# AstroEQ_PTH_MK3.net
KiCad netlist of a schematic drawn in EAGLE
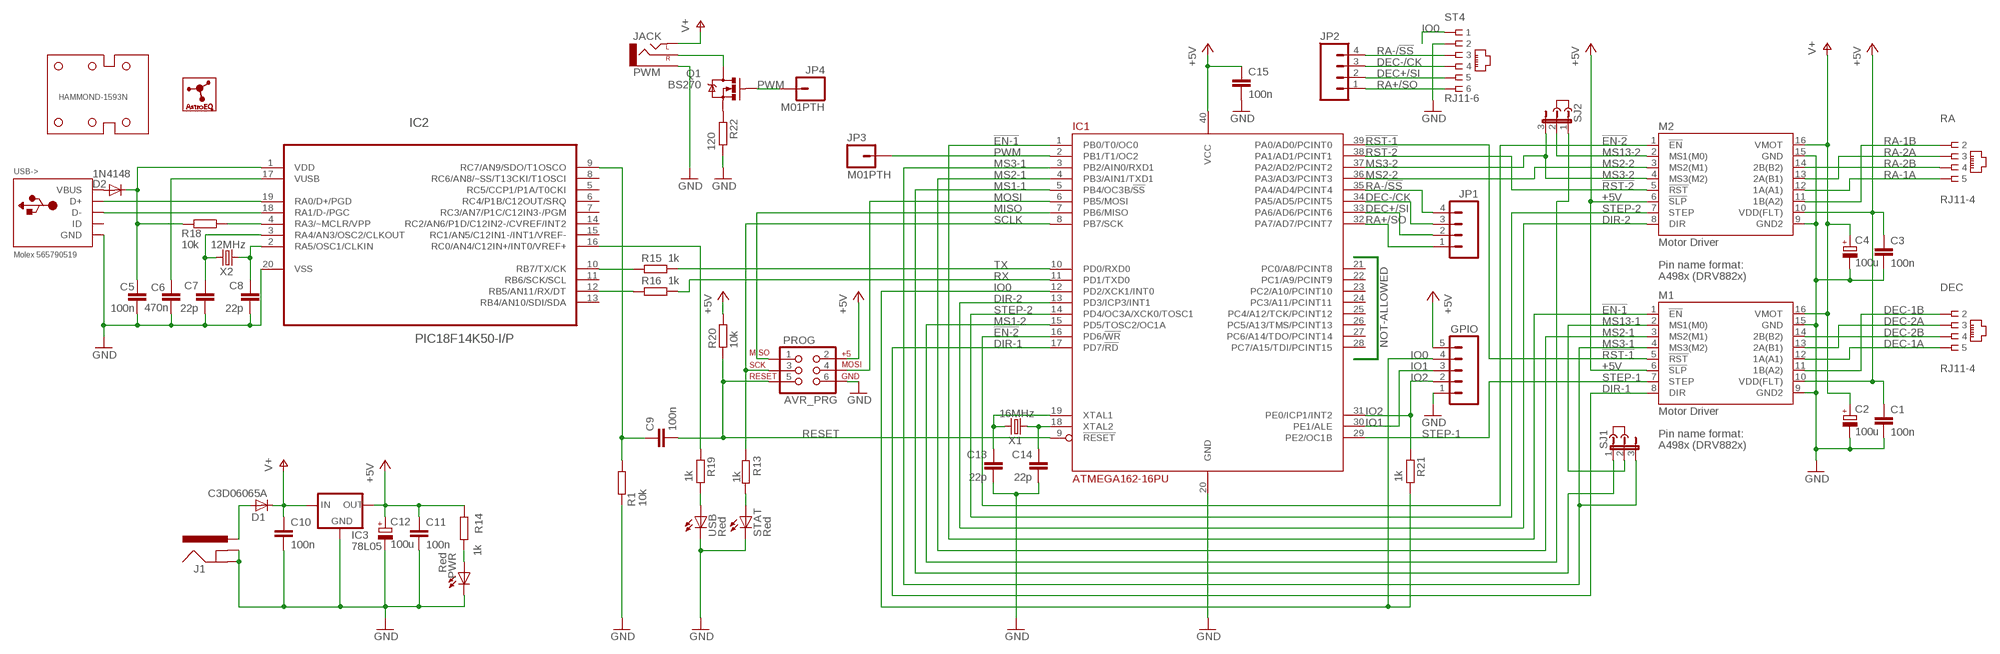
[diagram p0: schematic, sheet 1]

(export (version "E")
  (design (tool "Eeschema 10.0.6"))
  (components
    (comp (ref "C1")
      (value "100n")
      (footprint "eagle-import:C025-024X044")
      (fields (field (name "MF") "AVX") (field (name "MPN") "SR205C104KAR"))
      (libsource (lib "eagle-import") (part "C-EU025-024X044"))
    )
    (comp (ref "C2")
      (value "100u")
      (footprint "eagle-import:E2,5-7")
      (fields (field (name "MF") "MULTICOMP") (field (name "MPN") "MCGPR25V107M6.3X11"))
      (libsource (lib "eagle-import") (part "CPOL-EUE2.5-7"))
    )
    (comp (ref "C3")
      (value "100n")
      (footprint "eagle-import:C025-024X044")
      (fields (field (name "MF") "AVX") (field (name "MPN") "SR205C104KAR"))
      (libsource (lib "eagle-import") (part "C-EU025-024X044"))
    )
    (comp (ref "C4")
      (value "100u")
      (footprint "eagle-import:E2,5-7")
      (fields (field (name "MF") "MULTICOMP") (field (name "MPN") "MCGPR25V107M6.3X11"))
      (libsource (lib "eagle-import") (part "CPOL-EUE2.5-7"))
    )
    (comp (ref "C5")
      (value "100n")
      (footprint "eagle-import:C025-024X044")
      (fields (field (name "MF") "AVX") (field (name "MPN") "SR205C104KAR"))
      (libsource (lib "eagle-import") (part "C-EU025-024X044"))
    )
    (comp (ref "C6")
      (value "470n")
      (footprint "eagle-import:C025-024X044")
      (fields (field (name "MF") "KEMET") (field (name "MPN") "C320C474M5U5TA"))
      (libsource (lib "eagle-import") (part "C-EU025-024X044"))
    )
    (comp (ref "C7")
      (value "22p")
      (footprint "eagle-import:C025-024X044")
      (fields (field (name "MF") "AVX") (field (name "MPN") "SR151A220JAR"))
      (libsource (lib "eagle-import") (part "C-EU025-024X044"))
    )
    (comp (ref "C8")
      (value "22p")
      (footprint "eagle-import:C025-024X044")
      (fields (field (name "MF") "AVX") (field (name "MPN") "SR151A220JAR"))
      (libsource (lib "eagle-import") (part "C-EU025-024X044"))
    )
    (comp (ref "C9")
      (value "100n")
      (footprint "eagle-import:C025-024X044")
      (fields (field (name "MF") "AVX") (field (name "MPN") "SR205C104KAR"))
      (libsource (lib "eagle-import") (part "C-EU025-024X044"))
    )
    (comp (ref "C10")
      (value "100n")
      (footprint "eagle-import:C025-024X044")
      (fields (field (name "MF") "AVX") (field (name "MPN") "SR205C104KAR"))
      (libsource (lib "eagle-import") (part "C-EU025-024X044"))
    )
    (comp (ref "C11")
      (value "100n")
      (footprint "eagle-import:C025-024X044")
      (fields (field (name "MF") "AVX") (field (name "MPN") "SR205C104KAR"))
      (libsource (lib "eagle-import") (part "C-EU025-024X044"))
    )
    (comp (ref "C12")
      (value "100u")
      (footprint "eagle-import:E2,5-7")
      (fields (field (name "MF") "MULTICOMP") (field (name "MPN") "MCGPR25V107M6.3X11"))
      (libsource (lib "eagle-import") (part "CPOL-EUE2.5-7"))
    )
    (comp (ref "C13")
      (value "22p")
      (footprint "eagle-import:C025-024X044")
      (fields (field (name "MF") "AVX") (field (name "MPN") "SR151A220JAR"))
      (libsource (lib "eagle-import") (part "C-EU025-024X044"))
    )
    (comp (ref "C14")
      (value "22p")
      (footprint "eagle-import:C025-024X044")
      (fields (field (name "MF") "AVX") (field (name "MPN") "SR151A220JAR"))
      (libsource (lib "eagle-import") (part "C-EU025-024X044"))
    )
    (comp (ref "C15")
      (value "100n")
      (footprint "eagle-import:C025-024X044")
      (fields (field (name "MF") "AVX") (field (name "MPN") "SR205C104KAR"))
      (libsource (lib "eagle-import") (part "C-EU025-024X044"))
    )
    (comp (ref "D1")
      (value "C3D06065A")
      (footprint "eagle-import:C221B1A")
      (fields (field (name "MF") "WOLFSPEED"))
      (libsource (lib "eagle-import") (part "MUR820"))
    )
    (comp (ref "D2")
      (value "1N4148")
      (footprint "eagle-import:DIODE-1N4148")
      (fields (field (name "MF") "MULTICOMP") (field (name "MPN") "1N4148."))
      (libsource (lib "eagle-import") (part "DIODE1N4148"))
    )
    (comp (ref "DEC")
      (value "RJ11-4")
      (footprint "eagle-import:RJ11-NO_SHIELD-4")
      (fields (field (name "MF") "MOLEX") (field (name "MPN") "95501-2641"))
      (libsource (lib "eagle-import") (part "RJ11-4"))
    )
    (comp (ref "GPIO")
      (value "M05PTH")
      (footprint "eagle-import:1X05")
      (fields (field (name "MF") "CYNERGY3") (field (name "MPN") "SSF211X050"))
      (libsource (lib "eagle-import") (part "M05PTH"))
    )
    (comp (ref "HAMMOND-1593N")
      (value "HAMMOND-1593N-4HOLE")
      (footprint "eagle-import:HAMMOND-1593N4HOLES")
      (fields (field (name "MF") "HAMMOND") (field (name "MPN") "1593NBK"))
      (libsource (lib "eagle-import") (part "HAMMOND-1593N-4HOLE"))
    )
    (comp (ref "IC1")
      (value "ATMEGA162-16PU")
      (footprint "eagle-import:DIL40")
      (fields (field (name "MF") "ATMEL"))
      (libsource (lib "eagle-import") (part "ATMEGA162-16PU"))
    )
    (comp (ref "IC2")
      (value "PIC18F14K50-I/P")
      (footprint "eagle-import:DIL20")
      (fields (field (name "MF") "MICROCHIP"))
      (libsource (lib "eagle-import") (part "PIC18F14K50-I/P"))
    )
    (comp (ref "IC3")
      (value "78L05")
      (footprint "eagle-import:TO-92")
      (fields (field (name "MF") "FAIRCHILD SEMICONDUCTOR") (field (name "MPN") "LM78L05ACZX"))
      (libsource (lib "eagle-import") (part "V_REG_78XXTO-92"))
    )
    (comp (ref "J1")
      (value "POWER_JACKPTH")
      (footprint "eagle-import:POWER_JACK_PTH")
      (fields (field (name "MF") "MULTICOMP") (field (name "MPN") "MJ-179PH"))
      (libsource (lib "eagle-import") (part "POWER_JACKPTH"))
    )
    (comp (ref "J2")
      (value "JUMPER")
      (footprint "eagle-import:JUMP")
      (libsource (lib "eagle-import") (part "JUMPER"))
    )
    (comp (ref "J3")
      (value "JUMPER")
      (footprint "eagle-import:JUMP")
      (libsource (lib "eagle-import") (part "JUMPER"))
    )
    (comp (ref "JP1")
      (value "M04PTH")
      (footprint "eagle-import:1X04")
      (libsource (lib "eagle-import") (part "M04PTH"))
    )
    (comp (ref "JP2")
      (value "M04PTH")
      (footprint "eagle-import:1X04")
      (libsource (lib "eagle-import") (part "M04PTH"))
    )
    (comp (ref "JP3")
      (value "M01PTH")
      (footprint "eagle-import:1X01")
      (libsource (lib "eagle-import") (part "M01PTH"))
    )
    (comp (ref "JP4")
      (value "M01PTH")
      (footprint "eagle-import:1X01")
      (libsource (lib "eagle-import") (part "M01PTH"))
    )
    (comp (ref "LOGO1")
      (value "ASTROEQ5MM")
      (footprint "eagle-import:ASTROEQ-SMALL")
      (libsource (lib "eagle-import") (part "ASTROEQ5MM"))
    )
    (comp (ref "M1")
      (value "Motor Driver")
      (footprint "eagle-import:DIP16-W")
      (fields (field (name "MF") "SAMTEC") (field (name "MPN") "CES-116-01-T-S"))
      (libsource (lib "eagle-import") (part "A4983CARRIER"))
    )
    (comp (ref "M2")
      (value "Motor Driver")
      (footprint "eagle-import:DIP16-W")
      (fields (field (name "MF") "SAMTEC") (field (name "MPN") "CES-116-01-T-S"))
      (libsource (lib "eagle-import") (part "A4983CARRIER"))
    )
    (comp (ref "PROG")
      (value "AVR_PRG")
      (footprint "eagle-import:2X3")
      (fields (field (name "MF") "TE CONNECTIVITY / AMP") (field (name "MPN") "826632-3"))
      (libsource (lib "eagle-import") (part "AVR_SPI_PRG_6PTH"))
    )
    (comp (ref "PWM")
      (value "JACK")
      (footprint "eagle-import:AUDIO-JACK")
      (fields (field (name "MF") "CLIFF ELECTRONIC COMPONENTS") (field (name "MPN") "FC68131"))
      (libsource (lib "eagle-import") (part "AUDIO-JACKPTH"))
    )
    (comp (ref "PWR")
      (value "Red")
      (footprint "eagle-import:LED3MM")
      (fields (field (name "MF") "KINGBRIGHT") (field (name "MPN") "L-424HDT"))
      (libsource (lib "eagle-import") (part "LED3MM"))
    )
    (comp (ref "Q1")
      (value "BS270")
      (footprint "eagle-import:TO-92")
      (fields (field (name "MF") "FAIRCHILD SEMICONDUCTOR"))
      (libsource (lib "eagle-import") (part "MOSFET-NCHANNELPTH"))
    )
    (comp (ref "R1")
      (value "10k")
      (footprint "eagle-import:0204_7")
      (fields (field (name "MF") "MULTICOMP") (field (name "MPN") "MF12 10K"))
      (libsource (lib "eagle-import") (part "R-EU_0204/7"))
    )
    (comp (ref "R13")
      (value "1k")
      (footprint "eagle-import:0204_7")
      (fields (field (name "MF") "MULTICOMP") (field (name "MPN") "MF12 1K"))
      (libsource (lib "eagle-import") (part "R-EU_0204/7"))
    )
    (comp (ref "R14")
      (value "1k")
      (footprint "eagle-import:0204_7")
      (fields (field (name "MF") "MULTICOMP") (field (name "MPN") "MF12 1K"))
      (libsource (lib "eagle-import") (part "R-EU_0204/7"))
    )
    (comp (ref "R15")
      (value "1k")
      (footprint "eagle-import:0204_7")
      (fields (field (name "MF") "MULTICOMP") (field (name "MPN") "MF12 1K"))
      (libsource (lib "eagle-import") (part "R-EU_0204/7"))
    )
    (comp (ref "R16")
      (value "1k")
      (footprint "eagle-import:0204_7")
      (fields (field (name "MF") "MULTICOMP") (field (name "MPN") "MF12 1K"))
      (libsource (lib "eagle-import") (part "R-EU_0204/7"))
    )
    (comp (ref "R18")
      (value "10k")
      (footprint "eagle-import:0204_7")
      (fields (field (name "MF") "MULTICOMP") (field (name "MPN") "MF12 10K"))
      (libsource (lib "eagle-import") (part "R-EU_0204/7"))
    )
    (comp (ref "R19")
      (value "1k")
      (footprint "eagle-import:0204_7")
      (fields (field (name "MF") "MULTICOMP") (field (name "MPN") "MF12 1K"))
      (libsource (lib "eagle-import") (part "R-EU_0204/7"))
    )
    (comp (ref "R20")
      (value "10k")
      (footprint "eagle-import:0204_7")
      (fields (field (name "MF") "MULTICOMP") (field (name "MPN") "MF12 10K"))
      (libsource (lib "eagle-import") (part "R-EU_0204/7"))
    )
    (comp (ref "R21")
      (value "1k")
      (footprint "eagle-import:0204_7")
      (fields (field (name "MF") "MULTICOMP") (field (name "MPN") "MF12 1K"))
      (libsource (lib "eagle-import") (part "R-EU_0204/7"))
    )
    (comp (ref "R22")
      (value "120")
      (footprint "eagle-import:0204_7")
      (fields (field (name "MF") "MULTICOMP") (field (name "MPN") "MF12 120R"))
      (libsource (lib "eagle-import") (part "R-EU_0204/7"))
    )
    (comp (ref "RA")
      (value "RJ11-4")
      (footprint "eagle-import:RJ11-NO_SHIELD-4")
      (fields (field (name "MF") "MOLEX") (field (name "MPN") "95501-2641"))
      (libsource (lib "eagle-import") (part "RJ11-4"))
    )
    (comp (ref "SJ1")
      (value "JP2E")
      (footprint "eagle-import:JP2")
      (libsource (lib "eagle-import") (part "JP2E"))
    )
    (comp (ref "SJ2")
      (value "JP2EL")
      (footprint "eagle-import:JP2L")
      (libsource (lib "eagle-import") (part "JP2EL"))
    )
    (comp (ref "ST4")
      (value "RJ11-6")
      (footprint "eagle-import:RJ11-NO_SHIELD")
      (fields
        (field (name "MF") "TYCO ELECTRONICS")
        (field (name "MPN") "RJ11-2L-B")
        (field (name "MF_1") "MOLEX")
        (field (name "MPN_1") "95501-2661")
        (field (name "OC_FARNELL") "1536490")
      )
      (libsource (lib "eagle-import") (part "RJ11-2L-B"))
    )
    (comp (ref "STAT")
      (value "Red")
      (footprint "eagle-import:LED3MM")
      (fields (field (name "MF") "KINGBRIGHT") (field (name "MPN") "L-424HDT"))
      (libsource (lib "eagle-import") (part "LED3MM"))
    )
    (comp (ref "USB")
      (value "Red")
      (footprint "eagle-import:LED3MM")
      (fields (field (name "MF") "KINGBRIGHT") (field (name "MPN") "L-424HDT"))
      (libsource (lib "eagle-import") (part "LED3MM"))
    )
    (comp (ref "USB->")
      (value "Molex 565790519")
      (footprint "eagle-import:USB-MINIB-THM-MOLEX")
      (fields (field (name "MF") "MOLEX") (field (name "MPN") "565790519"))
      (libsource (lib "eagle-import") (part "USBMOLEX"))
    )
    (comp (ref "X1")
      (value "16MHz")
      (footprint "eagle-import:HC49US")
      (fields (field (name "MF") "TXC") (field (name "MPN") "9B-16.000MEEJ-B"))
      (libsource (lib "eagle-import") (part "CRYSTALHC49US"))
    )
    (comp (ref "X2")
      (value "12MHz")
      (footprint "eagle-import:HC49US")
      (fields (field (name "MF") "TXC") (field (name "MPN") "9B-12.000MAAJ-B"))
      (libsource (lib "eagle-import") (part "CRYSTALHC49US"))
    )
  )
  (nets
    (net (code "1") (name "+5V") (class "Default")
      (node (ref "C1") (pin "1") (pinfunction "1_1") (pintype "passive"))
      (node (ref "C11") (pin "1") (pinfunction "1_1") (pintype "passive"))
      (node (ref "C12") (pin "+") (pinfunction "+_+") (pintype "passive"))
      (node (ref "C15") (pin "1") (pinfunction "1_1") (pintype "passive"))
      (node (ref "C3") (pin "1") (pinfunction "1_1") (pintype "passive"))
      (node (ref "GPIO") (pin "5") (pinfunction "5_5") (pintype "passive"))
      (node (ref "IC1") (pin "40") (pinfunction "VCC_40") (pintype "power_in"))
      (node (ref "IC3") (pin "1") (pinfunction "OUT_1") (pintype "power_in"))
      (node (ref "M1") (pin "10") (pinfunction "VDD(FLT)_10") (pintype "power_in"))
      (node (ref "M1") (pin "6") (pinfunction "~{SLP}_6") (pintype "input"))
      (node (ref "M2") (pin "10") (pinfunction "VDD(FLT)_10") (pintype "power_in"))
      (node (ref "M2") (pin "6") (pinfunction "~{SLP}_6") (pintype "input"))
      (node (ref "PROG") (pin "2") (pinfunction "2_2") (pintype "passive"))
      (node (ref "R14") (pin "1") (pinfunction "1_1") (pintype "passive"))
      (node (ref "R20") (pin "2") (pinfunction "2_2") (pintype "passive"))
    )
    (net (code "2") (name "/DEC+{slash}SI") (class "Default")
      (node (ref "IC1") (pin "33") (pinfunction "PA6/AD6/PCINT6_33") (pintype "bidirectional"))
      (node (ref "JP1") (pin "2") (pinfunction "2_2") (pintype "passive"))
      (node (ref "JP2") (pin "2") (pinfunction "2_2") (pintype "passive"))
      (node (ref "ST4") (pin "5") (pinfunction "5_5") (pintype "passive"))
    )
    (net (code "3") (name "/DEC-1A") (class "Default")
      (node (ref "DEC") (pin "5") (pinfunction "5_5") (pintype "passive"))
      (node (ref "M1") (pin "12") (pinfunction "1A(A1)_12") (pintype "output"))
    )
    (net (code "4") (name "/DEC-1B") (class "Default")
      (node (ref "DEC") (pin "2") (pinfunction "2_2") (pintype "passive"))
      (node (ref "M1") (pin "11") (pinfunction "1B(A2)_11") (pintype "output"))
    )
    (net (code "5") (name "/DEC-2A") (class "Default")
      (node (ref "DEC") (pin "3") (pinfunction "3_3") (pintype "passive"))
      (node (ref "M1") (pin "13") (pinfunction "2A(B1)_13") (pintype "output"))
    )
    (net (code "6") (name "/DEC-2B") (class "Default")
      (node (ref "DEC") (pin "4") (pinfunction "4_4") (pintype "passive"))
      (node (ref "M1") (pin "14") (pinfunction "2B(B2)_14") (pintype "output"))
    )
    (net (code "7") (name "/DEC-{slash}CK") (class "Default")
      (node (ref "IC1") (pin "34") (pinfunction "PA5/AD5/PCINT5_34") (pintype "bidirectional"))
      (node (ref "JP1") (pin "3") (pinfunction "3_3") (pintype "passive"))
      (node (ref "JP2") (pin "3") (pinfunction "3_3") (pintype "passive"))
      (node (ref "ST4") (pin "4") (pinfunction "4_4") (pintype "passive"))
    )
    (net (code "8") (name "/DIR-1") (class "Default")
      (node (ref "IC1") (pin "17") (pinfunction "PD7/~{RD}_17") (pintype "bidirectional"))
      (node (ref "M1") (pin "8") (pinfunction "DIR_8") (pintype "input"))
    )
    (net (code "9") (name "/DIR-2") (class "Default")
      (node (ref "IC1") (pin "13") (pinfunction "PD3/ICP3/INT1_13") (pintype "bidirectional"))
      (node (ref "M2") (pin "8") (pinfunction "DIR_8") (pintype "input"))
    )
    (net (code "10") (name "/IO0") (class "Default")
      (node (ref "GPIO") (pin "4") (pinfunction "4_4") (pintype "passive"))
      (node (ref "IC1") (pin "12") (pinfunction "PD2/XCK1/INT0_12") (pintype "bidirectional"))
      (node (ref "R21") (pin "1") (pinfunction "1_1") (pintype "passive"))
      (node (ref "ST4") (pin "1") (pinfunction "1_1") (pintype "passive"))
    )
    (net (code "11") (name "/IO1") (class "Default")
      (node (ref "GPIO") (pin "3") (pinfunction "3_3") (pintype "passive"))
      (node (ref "IC1") (pin "30") (pinfunction "PE1/ALE_30") (pintype "bidirectional"))
    )
    (net (code "12") (name "/IO2") (class "Default")
      (node (ref "GPIO") (pin "2") (pinfunction "2_2") (pintype "passive"))
      (node (ref "IC1") (pin "31") (pinfunction "PE0/ICP1/INT2_31") (pintype "bidirectional"))
      (node (ref "R21") (pin "2") (pinfunction "2_2") (pintype "passive"))
    )
    (net (code "13") (name "/MISO") (class "Default")
      (node (ref "IC1") (pin "7") (pinfunction "PB6/MISO_7") (pintype "bidirectional"))
      (node (ref "PROG") (pin "1") (pinfunction "1_1") (pintype "passive"))
    )
    (net (code "14") (name "/MOSI") (class "Default")
      (node (ref "IC1") (pin "6") (pinfunction "PB5/MOSI_6") (pintype "bidirectional"))
      (node (ref "PROG") (pin "4") (pinfunction "4_4") (pintype "passive"))
    )
    (net (code "15") (name "/MS1-1") (class "Default")
      (node (ref "IC1") (pin "5") (pinfunction "PB4/OC3B/~{SS}_5") (pintype "bidirectional"))
      (node (ref "SJ1") (pin "1") (pinfunction "1_1") (pintype "passive"))
    )
    (net (code "16") (name "/MS1-2") (class "Default")
      (node (ref "IC1") (pin "15") (pinfunction "PD5/TOSC2/OC1A_15") (pintype "bidirectional"))
      (node (ref "SJ2") (pin "1") (pinfunction "1_1") (pintype "passive"))
    )
    (net (code "17") (name "/MS2-1") (class "Default")
      (node (ref "IC1") (pin "4") (pinfunction "PB3/AIN1/TXD1_4") (pintype "bidirectional"))
      (node (ref "M1") (pin "3") (pinfunction "MS2(M1)_3") (pintype "input"))
    )
    (net (code "18") (name "/MS2-2") (class "Default")
      (node (ref "IC1") (pin "36") (pinfunction "PA3/AD3/PCINT3_36") (pintype "bidirectional"))
      (node (ref "M2") (pin "3") (pinfunction "MS2(M1)_3") (pintype "input"))
    )
    (net (code "19") (name "/MS3-1") (class "Default")
      (node (ref "IC1") (pin "3") (pinfunction "PB2/AIN0/RXD1_3") (pintype "bidirectional"))
      (node (ref "M1") (pin "4") (pinfunction "MS3(M2)_4") (pintype "input"))
      (node (ref "SJ1") (pin "3") (pinfunction "3_3") (pintype "passive"))
    )
    (net (code "20") (name "/MS3-2") (class "Default")
      (node (ref "IC1") (pin "37") (pinfunction "PA2/AD2/PCINT2_37") (pintype "bidirectional"))
      (node (ref "M2") (pin "4") (pinfunction "MS3(M2)_4") (pintype "input"))
      (node (ref "SJ2") (pin "3") (pinfunction "3_3") (pintype "passive"))
    )
    (net (code "21") (name "/MS13-1") (class "Default")
      (node (ref "M1") (pin "2") (pinfunction "MS1(M0)_2") (pintype "input"))
      (node (ref "SJ1") (pin "2") (pinfunction "2_2") (pintype "passive"))
    )
    (net (code "22") (name "/MS13-2") (class "Default")
      (node (ref "M2") (pin "2") (pinfunction "MS1(M0)_2") (pintype "input"))
      (node (ref "SJ2") (pin "2") (pinfunction "2_2") (pintype "passive"))
    )
    (net (code "23") (name "/PWM") (class "Default")
      (node (ref "IC1") (pin "2") (pinfunction "PB1/T1/OC2_2") (pintype "bidirectional"))
      (node (ref "JP3") (pin "1") (pinfunction "1_1") (pintype "passive"))
      (node (ref "JP4") (pin "1") (pinfunction "1_1") (pintype "passive"))
      (node (ref "Q1") (pin "2") (pinfunction "G_2") (pintype "passive"))
    )
    (net (code "24") (name "/RA+{slash}SO") (class "Default")
      (node (ref "IC1") (pin "32") (pinfunction "PA7/AD7/PCINT7_32") (pintype "bidirectional"))
      (node (ref "JP1") (pin "1") (pinfunction "1_1") (pintype "passive"))
      (node (ref "JP2") (pin "1") (pinfunction "1_1") (pintype "passive"))
      (node (ref "ST4") (pin "6") (pinfunction "6_6") (pintype "passive"))
    )
    (net (code "25") (name "/RA-1A") (class "Default")
      (node (ref "M2") (pin "12") (pinfunction "1A(A1)_12") (pintype "output"))
      (node (ref "RA") (pin "5") (pinfunction "5_5") (pintype "passive"))
    )
    (net (code "26") (name "/RA-1B") (class "Default")
      (node (ref "M2") (pin "11") (pinfunction "1B(A2)_11") (pintype "output"))
      (node (ref "RA") (pin "2") (pinfunction "2_2") (pintype "passive"))
    )
    (net (code "27") (name "/RA-2A") (class "Default")
      (node (ref "M2") (pin "13") (pinfunction "2A(B1)_13") (pintype "output"))
      (node (ref "RA") (pin "3") (pinfunction "3_3") (pintype "passive"))
    )
    (net (code "28") (name "/RA-2B") (class "Default")
      (node (ref "M2") (pin "14") (pinfunction "2B(B2)_14") (pintype "output"))
      (node (ref "RA") (pin "4") (pinfunction "4_4") (pintype "passive"))
    )
    (net (code "29") (name "/RA-{slash}~{SS}") (class "Default")
      (node (ref "IC1") (pin "35") (pinfunction "PA4/AD4/PCINT4_35") (pintype "bidirectional"))
      (node (ref "JP1") (pin "4") (pinfunction "4_4") (pintype "passive"))
      (node (ref "JP2") (pin "4") (pinfunction "4_4") (pintype "passive"))
      (node (ref "ST4") (pin "3") (pinfunction "3_3") (pintype "passive"))
    )
    (net (code "30") (name "/RESET") (class "Default")
      (node (ref "C9") (pin "2") (pinfunction "2_2") (pintype "passive"))
      (node (ref "IC1") (pin "9") (pinfunction "~{RESET}_9") (pintype "input"))
      (node (ref "PROG") (pin "5") (pinfunction "5_5") (pintype "passive"))
      (node (ref "R20") (pin "1") (pinfunction "1_1") (pintype "passive"))
    )
    (net (code "31") (name "/RX") (class "Default")
      (node (ref "IC1") (pin "11") (pinfunction "PD1/TXD0_11") (pintype "bidirectional"))
      (node (ref "R16") (pin "1") (pinfunction "1_1") (pintype "passive"))
    )
    (net (code "32") (name "/SCLK") (class "Default")
      (node (ref "IC1") (pin "8") (pinfunction "PB7/SCK_8") (pintype "bidirectional"))
      (node (ref "PROG") (pin "3") (pinfunction "3_3") (pintype "passive"))
      (node (ref "R13") (pin "1") (pinfunction "1_1") (pintype "passive"))
    )
    (net (code "33") (name "/STEP-1") (class "Default")
      (node (ref "IC1") (pin "29") (pinfunction "PE2/OC1B_29") (pintype "bidirectional"))
      (node (ref "M1") (pin "7") (pinfunction "STEP_7") (pintype "input"))
    )
    (net (code "34") (name "/STEP-2") (class "Default")
      (node (ref "IC1") (pin "14") (pinfunction "PD4/OC3A/XCK0/TOSC1_14") (pintype "bidirectional"))
      (node (ref "M2") (pin "7") (pinfunction "STEP_7") (pintype "input"))
    )
    (net (code "35") (name "/TX") (class "Default")
      (node (ref "IC1") (pin "10") (pinfunction "PD0/RXD0_10") (pintype "bidirectional"))
      (node (ref "R15") (pin "1") (pinfunction "1_1") (pintype "passive"))
    )
    (net (code "36") (name "/~{EN-1}") (class "Default")
      (node (ref "IC1") (pin "1") (pinfunction "PB0/T0/OC0_1") (pintype "bidirectional"))
      (node (ref "M1") (pin "1") (pinfunction "~{EN}_1") (pintype "input"))
    )
    (net (code "37") (name "/~{EN-2}") (class "Default")
      (node (ref "IC1") (pin "16") (pinfunction "PD6/~{WR}_16") (pintype "bidirectional"))
      (node (ref "M2") (pin "1") (pinfunction "~{EN}_1") (pintype "input"))
    )
    (net (code "39") (name "/~{RST-1}") (class "Default")
      (node (ref "IC1") (pin "39") (pinfunction "PA0/AD0/PCINT0_39") (pintype "bidirectional"))
      (node (ref "M1") (pin "5") (pinfunction "~{RST}_5") (pintype "input"))
    )
    (net (code "40") (name "/~{RST-2}") (class "Default")
      (node (ref "IC1") (pin "38") (pinfunction "PA1/AD1/PCINT1_38") (pintype "bidirectional"))
      (node (ref "M2") (pin "5") (pinfunction "~{RST}_5") (pintype "input"))
    )
    (net (code "41") (name "GND") (class "Default")
      (node (ref "C1") (pin "2") (pinfunction "2_2") (pintype "passive"))
      (node (ref "C10") (pin "2") (pinfunction "2_2") (pintype "passive"))
      (node (ref "C11") (pin "2") (pinfunction "2_2") (pintype "passive"))
      (node (ref "C12") (pin "-") (pinfunction "-_-") (pintype "passive"))
      (node (ref "C13") (pin "2") (pinfunction "2_2") (pintype "passive"))
      (node (ref "C14") (pin "2") (pinfunction "2_2") (pintype "passive"))
      (node (ref "C15") (pin "2") (pinfunction "2_2") (pintype "passive"))
      (node (ref "C2") (pin "-") (pinfunction "-_-") (pintype "passive"))
      (node (ref "C3") (pin "2") (pinfunction "2_2") (pintype "passive"))
      (node (ref "C4") (pin "-") (pinfunction "-_-") (pintype "passive"))
      (node (ref "C5") (pin "2") (pinfunction "2_2") (pintype "passive"))
      (node (ref "C6") (pin "1") (pinfunction "1_1") (pintype "passive"))
      (node (ref "C7") (pin "2") (pinfunction "2_2") (pintype "passive"))
      (node (ref "C8") (pin "2") (pinfunction "2_2") (pintype "passive"))
      (node (ref "GPIO") (pin "1") (pinfunction "1_1") (pintype "passive"))
      (node (ref "IC1") (pin "20") (pinfunction "GND_20") (pintype "power_in"))
      (node (ref "IC2") (pin "20") (pinfunction "VSS_20") (pintype "power_in"))
      (node (ref "IC3") (pin "2") (pinfunction "GND_2") (pintype "input"))
      (node (ref "J1") (pin "GND") (pinfunction "GND_GND") (pintype "bidirectional"))
      (node (ref "J1") (pin "GNDBREAK") (pinfunction "GNDBREAK_GNDBREAK") (pintype "bidirectional"))
      (node (ref "M1") (pin "15") (pinfunction "GND_15") (pintype "power_in"))
      (node (ref "M1") (pin "9") (pinfunction "GND2_9") (pintype "power_in"))
      (node (ref "M2") (pin "15") (pinfunction "GND_15") (pintype "power_in"))
      (node (ref "M2") (pin "9") (pinfunction "GND2_9") (pintype "power_in"))
      (node (ref "PROG") (pin "6") (pinfunction "6_6") (pintype "passive"))
      (node (ref "PWM") (pin "SLEEVE") (pinfunction "SLEEVE_SLEEVE") (pintype "bidirectional"))
      (node (ref "PWR") (pin "K") (pinfunction "C_K") (pintype "passive"))
      (node (ref "R1") (pin "2") (pinfunction "2_2") (pintype "passive"))
      (node (ref "R22") (pin "1") (pinfunction "1_1") (pintype "passive"))
      (node (ref "ST4") (pin "2") (pinfunction "2_2") (pintype "passive"))
      (node (ref "STAT") (pin "K") (pinfunction "C_K") (pintype "passive"))
      (node (ref "USB") (pin "K") (pinfunction "C_K") (pintype "passive"))
      (node (ref "USB->") (pin "GND") (pinfunction "GND_GND") (pintype "power_in"))
      (node (ref "USB->") (pin "GND1") (pinfunction "GND_GND1") (pintype "power_in"))
      (node (ref "USB->") (pin "GND4") (pinfunction "GND_GND4") (pintype "power_in"))
    )
    (net (code "42") (name "Net-(D1-PadA)") (class "Default")
      (node (ref "D1") (pin "A") (pinfunction "A_A") (pintype "passive"))
      (node (ref "J1") (pin "PWR") (pinfunction "PWR_PWR") (pintype "bidirectional"))
    )
    (net (code "43") (name "Net-(D2-PadA)") (class "Default")
      (node (ref "D2") (pin "A") (pinfunction "A_A") (pintype "passive"))
      (node (ref "USB->") (pin "VBUS") (pinfunction "VBUS_VBUS") (pintype "power_in"))
    )
    (net (code "44") (name "Net-(IC1-XTAL1)") (class "Default")
      (node (ref "C13") (pin "1") (pinfunction "1_1") (pintype "passive"))
      (node (ref "IC1") (pin "19") (pinfunction "XTAL1_19") (pintype "input"))
      (node (ref "X1") (pin "2") (pinfunction "2_2") (pintype "passive"))
    )
    (net (code "45") (name "Net-(IC1-XTAL2)") (class "Default")
      (node (ref "C14") (pin "1") (pinfunction "1_1") (pintype "passive"))
      (node (ref "IC1") (pin "18") (pinfunction "XTAL2_18") (pintype "input"))
      (node (ref "X1") (pin "1") (pinfunction "1_1") (pintype "passive"))
    )
    (net (code "46") (name "Net-(IC2-RA0{slash}D+{slash}PGD)") (class "Default")
      (node (ref "IC2") (pin "19") (pinfunction "RA0/D+/PGD_19") (pintype "bidirectional"))
      (node (ref "USB->") (pin "D+") (pinfunction "D+_D+") (pintype "bidirectional"))
    )
    (net (code "47") (name "Net-(IC2-RA1{slash}D-{slash}PGC)") (class "Default")
      (node (ref "IC2") (pin "18") (pinfunction "RA1/D-/PGC_18") (pintype "bidirectional"))
      (node (ref "USB->") (pin "D-") (pinfunction "D-_D-") (pintype "bidirectional"))
    )
    (net (code "48") (name "Net-(IC2-RA3{slash}~{MCLR{slash}VPP})") (class "Default")
      (node (ref "IC2") (pin "4") (pinfunction "RA3/~{MCLR/VPP}_4") (pintype "input"))
      (node (ref "R18") (pin "1") (pinfunction "1_1") (pintype "passive"))
    )
    (net (code "49") (name "Net-(IC2-RA4{slash}AN3{slash}OSC2{slash}CLKOUT)") (class "Default")
      (node (ref "C7") (pin "1") (pinfunction "1_1") (pintype "passive"))
      (node (ref "IC2") (pin "3") (pinfunction "RA4/AN3/OSC2/CLKOUT_3") (pintype "bidirectional"))
      (node (ref "X2") (pin "2") (pinfunction "2_2") (pintype "passive"))
    )
    (net (code "50") (name "Net-(IC2-RA5{slash}OSC1{slash}CLKIN)") (class "Default")
      (node (ref "C8") (pin "1") (pinfunction "1_1") (pintype "passive"))
      (node (ref "IC2") (pin "2") (pinfunction "RA5/OSC1/CLKIN_2") (pintype "bidirectional"))
      (node (ref "X2") (pin "1") (pinfunction "1_1") (pintype "passive"))
    )
    (net (code "51") (name "Net-(IC2-RB5{slash}AN11{slash}RX{slash}DT)") (class "Default")
      (node (ref "IC2") (pin "12") (pinfunction "RB5/AN11/RX/DT_12") (pintype "bidirectional"))
      (node (ref "R16") (pin "2") (pinfunction "2_2") (pintype "passive"))
    )
    (net (code "52") (name "Net-(IC2-RB7{slash}TX{slash}CK)") (class "Default")
      (node (ref "IC2") (pin "10") (pinfunction "RB7/TX/CK_10") (pintype "bidirectional"))
      (node (ref "R15") (pin "2") (pinfunction "2_2") (pintype "passive"))
    )
    (net (code "53") (name "Net-(IC2-RC0{slash}AN4{slash}C12IN+{slash}INT0{slash}VREF+)") (class "Default")
      (node (ref "IC2") (pin "16") (pinfunction "RC0/AN4/C12IN+/INT0/VREF+_16") (pintype "bidirectional"))
      (node (ref "R19") (pin "2") (pinfunction "2_2") (pintype "passive"))
    )
    (net (code "54") (name "Net-(IC2-RC7{slash}AN9{slash}SDO{slash}T1OSCO)") (class "Default")
      (node (ref "C9") (pin "1") (pinfunction "1_1") (pintype "passive"))
      (node (ref "IC2") (pin "9") (pinfunction "RC7/AN9/SDO/T1OSCO_9") (pintype "bidirectional"))
      (node (ref "R1") (pin "1") (pinfunction "1_1") (pintype "passive"))
    )
    (net (code "55") (name "Net-(IC2-VDD)") (class "Default")
      (node (ref "C5") (pin "1") (pinfunction "1_1") (pintype "passive"))
      (node (ref "D2") (pin "C") (pinfunction "C_C") (pintype "passive"))
      (node (ref "IC2") (pin "1") (pinfunction "VDD_1") (pintype "power_in"))
      (node (ref "R18") (pin "2") (pinfunction "2_2") (pintype "passive"))
    )
    (net (code "56") (name "Net-(IC2-VUSB)") (class "Default")
      (node (ref "C6") (pin "2") (pinfunction "2_2") (pintype "passive"))
      (node (ref "IC2") (pin "17") (pinfunction "VUSB_17") (pintype "power_in"))
    )
    (net (code "57") (name "Net-(PWM-RIGHT)") (class "Default")
      (node (ref "PWM") (pin "RING") (pinfunction "RIGHT_RING") (pintype "bidirectional"))
      (node (ref "Q1") (pin "1") (pinfunction "D_1") (pintype "passive"))
    )
    (net (code "58") (name "Net-(PWR-PadA)") (class "Default")
      (node (ref "PWR") (pin "A") (pinfunction "A_A") (pintype "passive"))
      (node (ref "R14") (pin "2") (pinfunction "2_2") (pintype "passive"))
    )
    (net (code "59") (name "Net-(Q1-S)") (class "Default")
      (node (ref "Q1") (pin "3") (pinfunction "S_3") (pintype "passive"))
      (node (ref "R22") (pin "2") (pinfunction "2_2") (pintype "passive"))
    )
    (net (code "60") (name "Net-(R13-Pad2)") (class "Default")
      (node (ref "R13") (pin "2") (pinfunction "2_2") (pintype "passive"))
      (node (ref "STAT") (pin "A") (pinfunction "A_A") (pintype "passive"))
    )
    (net (code "61") (name "Net-(R19-Pad1)") (class "Default")
      (node (ref "R19") (pin "1") (pinfunction "1_1") (pintype "passive"))
      (node (ref "USB") (pin "A") (pinfunction "A_A") (pintype "passive"))
    )
    (net (code "62") (name "V+") (class "Default")
      (node (ref "C10") (pin "1") (pinfunction "1_1") (pintype "passive"))
      (node (ref "C2") (pin "+") (pinfunction "+_+") (pintype "passive"))
      (node (ref "C4") (pin "+") (pinfunction "+_+") (pintype "passive"))
      (node (ref "D1") (pin "C") (pinfunction "C_C") (pintype "passive"))
      (node (ref "IC3") (pin "3") (pinfunction "IN_3") (pintype "input"))
      (node (ref "M1") (pin "16") (pinfunction "VMOT_16") (pintype "power_in"))
      (node (ref "M2") (pin "16") (pinfunction "VMOT_16") (pintype "power_in"))
      (node (ref "PWM") (pin "TIP") (pinfunction "LEFT_TIP") (pintype "bidirectional"))
    )
    (net (code "63") (name "unconnected-(IC1-PC0{slash}A8{slash}PCINT8-Pad21)") (class "Default")
      (node (ref "IC1") (pin "21") (pinfunction "PC0/A8/PCINT8_21") (pintype "bidirectional"))
    )
    (net (code "64") (name "unconnected-(IC1-PC1{slash}A9{slash}PCINT9-Pad22)") (class "Default")
      (node (ref "IC1") (pin "22") (pinfunction "PC1/A9/PCINT9_22") (pintype "bidirectional"))
    )
    (net (code "65") (name "unconnected-(IC1-PC2{slash}A10{slash}PCINT10-Pad23)") (class "Default")
      (node (ref "IC1") (pin "23") (pinfunction "PC2/A10/PCINT10_23") (pintype "bidirectional"))
    )
    (net (code "66") (name "unconnected-(IC1-PC3{slash}A11{slash}PCINT11-Pad24)") (class "Default")
      (node (ref "IC1") (pin "24") (pinfunction "PC3/A11/PCINT11_24") (pintype "bidirectional"))
    )
    (net (code "67") (name "unconnected-(IC1-PC4{slash}A12{slash}TCK{slash}PCINT12-Pad25)") (class "Default")
      (node (ref "IC1") (pin "25") (pinfunction "PC4/A12/TCK/PCINT12_25") (pintype "bidirectional"))
    )
    (net (code "68") (name "unconnected-(IC1-PC5{slash}A13{slash}TMS{slash}PCINT13-Pad26)") (class "Default")
      (node (ref "IC1") (pin "26") (pinfunction "PC5/A13/TMS/PCINT13_26") (pintype "bidirectional"))
    )
    (net (code "69") (name "unconnected-(IC1-PC6{slash}A14{slash}TDO{slash}PCINT14-Pad27)") (class "Default")
      (node (ref "IC1") (pin "27") (pinfunction "PC6/A14/TDO/PCINT14_27") (pintype "bidirectional"))
    )
    (net (code "70") (name "unconnected-(IC1-PC7{slash}A15{slash}TDI{slash}PCINT15-Pad28)") (class "Default")
      (node (ref "IC1") (pin "28") (pinfunction "PC7/A15/TDI/PCINT15_28") (pintype "bidirectional"))
    )
    (net (code "71") (name "unconnected-(IC2-RB4{slash}AN10{slash}SDI{slash}SDA-Pad13)") (class "Default")
      (node (ref "IC2") (pin "13") (pinfunction "RB4/AN10/SDI/SDA_13") (pintype "bidirectional"))
    )
    (net (code "72") (name "unconnected-(IC2-RB6{slash}SCK{slash}SCL-Pad11)") (class "Default")
      (node (ref "IC2") (pin "11") (pinfunction "RB6/SCK/SCL_11") (pintype "bidirectional"))
    )
    (net (code "73") (name "unconnected-(IC2-RC1{slash}AN5{slash}C12IN1-{slash}INT1{slash}VREF--Pad15)") (class "Default")
      (node (ref "IC2") (pin "15") (pinfunction "RC1/AN5/C12IN1-/INT1/VREF-_15") (pintype "bidirectional"))
    )
    (net (code "74") (name "unconnected-(IC2-RC2{slash}AN6{slash}P1D{slash}C12IN2-{slash}CVREF{slash}INT2-Pad14)") (class "Default")
      (node (ref "IC2") (pin "14") (pinfunction "RC2/AN6/P1D/C12IN2-/CVREF/INT2_14") (pintype "bidirectional"))
    )
    (net (code "75") (name "unconnected-(IC2-RC3{slash}AN7{slash}P1C{slash}C12IN3-{slash}PGM-Pad7)") (class "Default")
      (node (ref "IC2") (pin "7") (pinfunction "RC3/AN7/P1C/C12IN3-/PGM_7") (pintype "bidirectional"))
    )
    (net (code "76") (name "unconnected-(IC2-RC4{slash}P1B{slash}C12OUT{slash}SRQ-Pad6)") (class "Default")
      (node (ref "IC2") (pin "6") (pinfunction "RC4/P1B/C12OUT/SRQ_6") (pintype "bidirectional"))
    )
    (net (code "77") (name "unconnected-(IC2-RC5{slash}CCP1{slash}P1A{slash}T0CKI-Pad5)") (class "Default")
      (node (ref "IC2") (pin "5") (pinfunction "RC5/CCP1/P1A/T0CKI_5") (pintype "bidirectional"))
    )
    (net (code "78") (name "unconnected-(IC2-RC6{slash}AN8{slash}~{SS{slash}T13CKI{slash}T1OSCI}-Pad8)") (class "Default")
      (node (ref "IC2") (pin "8") (pinfunction "RC6/AN8/~{SS/T13CKI/T1OSCI}_8") (pintype "bidirectional"))
    )
    (net (code "79") (name "unconnected-(USB->-PadID)") (class "Default")
      (node (ref "USB->") (pin "ID") (pinfunction "ID_ID") (pintype "bidirectional"))
    )
  )
)
